# light_triggger.net
KiCad netlist of a schematic drawn in EAGLE
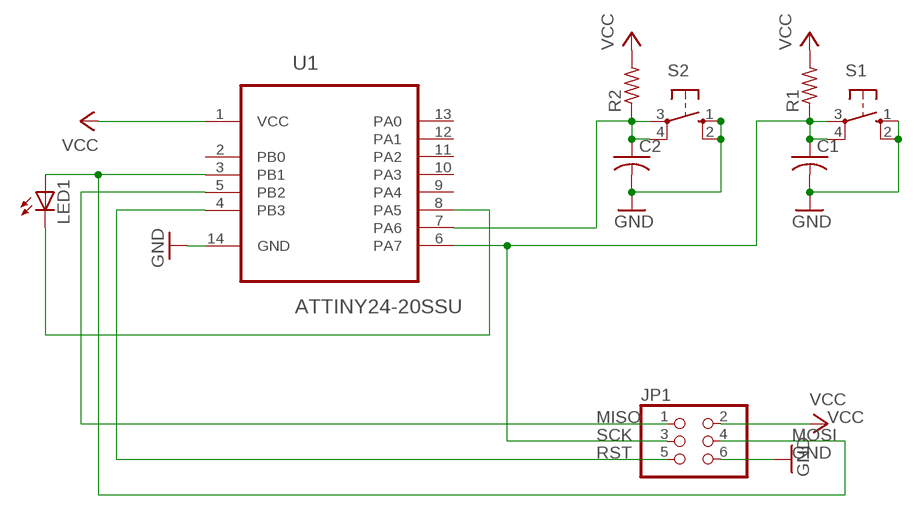
[diagram p0: schematic, sheet 1]

(export (version "E")
  (design (tool "Eeschema 10.0.6"))
  (components
    (comp (ref "C1")
      (value "C-USC0603K")
      (footprint "eagle-import:C0603K")
      (libsource (lib "eagle-import") (part "C-USC0603K"))
    )
    (comp (ref "C2")
      (value "C-USC0603K")
      (footprint "eagle-import:C0603K")
      (libsource (lib "eagle-import") (part "C-USC0603K"))
    )
    (comp (ref "JP1")
      (value "PINHD-2X3")
      (footprint "eagle-import:2X03")
      (libsource (lib "eagle-import") (part "PINHD-2X3"))
    )
    (comp (ref "LED1")
      (value "LED5MM")
      (footprint "eagle-import:LED5MM")
      (libsource (lib "eagle-import") (part "LED5MM"))
    )
    (comp (ref "R1")
      (value "R-US_R0603")
      (footprint "eagle-import:R0603")
      (libsource (lib "eagle-import") (part "R-US_R0603"))
    )
    (comp (ref "R2")
      (value "R-US_R0603")
      (footprint "eagle-import:R0603")
      (libsource (lib "eagle-import") (part "R-US_R0603"))
    )
    (comp (ref "S1")
      (value "10-XX")
      (footprint "eagle-import:B3F-10XX")
      (fields (field (name "MPN") "B3F-1000"))
      (libsource (lib "eagle-import") (part "10-XX"))
    )
    (comp (ref "S2")
      (value "10-XX")
      (footprint "eagle-import:B3F-10XX")
      (fields (field (name "MPN") "B3F-1000"))
      (libsource (lib "eagle-import") (part "10-XX"))
    )
    (comp (ref "U1")
      (value "ATTINY24-20SSU")
      (footprint "eagle-import:SOIC127P600X175-14N")
      (libsource (lib "eagle-import") (part "ATTINY24-20SSU"))
    )
  )
  (nets
    (net (code "1") (name "/MISO") (class "Default")
      (node (ref "JP1") (pin "1") (pinfunction "1_1") (pintype "passive"))
      (node (ref "U1") (pin "5") (pinfunction "PB2_5") (pintype "bidirectional"))
    )
    (net (code "2") (name "/MOSI") (class "Default")
      (node (ref "JP1") (pin "4") (pinfunction "4_4") (pintype "passive"))
      (node (ref "LED1") (pin "A") (pinfunction "A_A") (pintype "passive"))
      (node (ref "U1") (pin "3") (pinfunction "PB1_3") (pintype "bidirectional"))
    )
    (net (code "3") (name "/RST") (class "Default")
      (node (ref "JP1") (pin "5") (pinfunction "5_5") (pintype "passive"))
      (node (ref "U1") (pin "4") (pinfunction "PB3_4") (pintype "bidirectional"))
    )
    (net (code "4") (name "/SCK") (class "Default")
      (node (ref "C1") (pin "1") (pinfunction "1_1") (pintype "passive"))
      (node (ref "JP1") (pin "3") (pinfunction "3_3") (pintype "passive"))
      (node (ref "R1") (pin "1") (pinfunction "1_1") (pintype "passive"))
      (node (ref "S1") (pin "3") (pinfunction "P_3") (pintype "passive"))
      (node (ref "S1") (pin "4") (pinfunction "P1_4") (pintype "passive"))
      (node (ref "U1") (pin "6") (pinfunction "PA7_6") (pintype "bidirectional"))
    )
    (net (code "5") (name "GND") (class "Default")
      (node (ref "C1") (pin "2") (pinfunction "2_2") (pintype "passive"))
      (node (ref "C2") (pin "2") (pinfunction "2_2") (pintype "passive"))
      (node (ref "JP1") (pin "6") (pinfunction "6_6") (pintype "passive"))
      (node (ref "S1") (pin "1") (pinfunction "S_1") (pintype "passive"))
      (node (ref "S1") (pin "2") (pinfunction "S1_2") (pintype "passive"))
      (node (ref "S2") (pin "1") (pinfunction "S_1") (pintype "passive"))
      (node (ref "S2") (pin "2") (pinfunction "S1_2") (pintype "passive"))
      (node (ref "U1") (pin "14") (pinfunction "GND_14") (pintype "passive"))
    )
    (net (code "6") (name "Net-(LED1-C)") (class "Default")
      (node (ref "LED1") (pin "K") (pinfunction "C_K") (pintype "passive"))
      (node (ref "U1") (pin "8") (pinfunction "PA5_8") (pintype "bidirectional"))
    )
    (net (code "7") (name "Net-(S2-P)") (class "Default")
      (node (ref "C2") (pin "1") (pinfunction "1_1") (pintype "passive"))
      (node (ref "R2") (pin "1") (pinfunction "1_1") (pintype "passive"))
      (node (ref "S2") (pin "3") (pinfunction "P_3") (pintype "passive"))
      (node (ref "S2") (pin "4") (pinfunction "P1_4") (pintype "passive"))
      (node (ref "U1") (pin "7") (pinfunction "PA6_7") (pintype "bidirectional"))
    )
    (net (code "8") (name "VCC") (class "Default")
      (node (ref "JP1") (pin "2") (pinfunction "2_2") (pintype "passive"))
      (node (ref "R1") (pin "2") (pinfunction "2_2") (pintype "passive"))
      (node (ref "R2") (pin "2") (pinfunction "2_2") (pintype "passive"))
      (node (ref "U1") (pin "1") (pinfunction "VCC_1") (pintype "power_in"))
    )
    (net (code "9") (name "unconnected-(U1-PA0-Pad13)") (class "Default")
      (node (ref "U1") (pin "13") (pinfunction "PA0_13") (pintype "bidirectional"))
    )
    (net (code "10") (name "unconnected-(U1-PA1-Pad12)") (class "Default")
      (node (ref "U1") (pin "12") (pinfunction "PA1_12") (pintype "bidirectional"))
    )
    (net (code "11") (name "unconnected-(U1-PA2-Pad11)") (class "Default")
      (node (ref "U1") (pin "11") (pinfunction "PA2_11") (pintype "bidirectional"))
    )
    (net (code "12") (name "unconnected-(U1-PA3-Pad10)") (class "Default")
      (node (ref "U1") (pin "10") (pinfunction "PA3_10") (pintype "bidirectional"))
    )
    (net (code "13") (name "unconnected-(U1-PA4-Pad9)") (class "Default")
      (node (ref "U1") (pin "9") (pinfunction "PA4_9") (pintype "bidirectional"))
    )
    (net (code "14") (name "unconnected-(U1-PB0-Pad2)") (class "Default")
      (node (ref "U1") (pin "2") (pinfunction "PB0_2") (pintype "bidirectional"))
    )
  )
)
